# Riser.net
KiCad netlist of a schematic drawn in Altium Designer
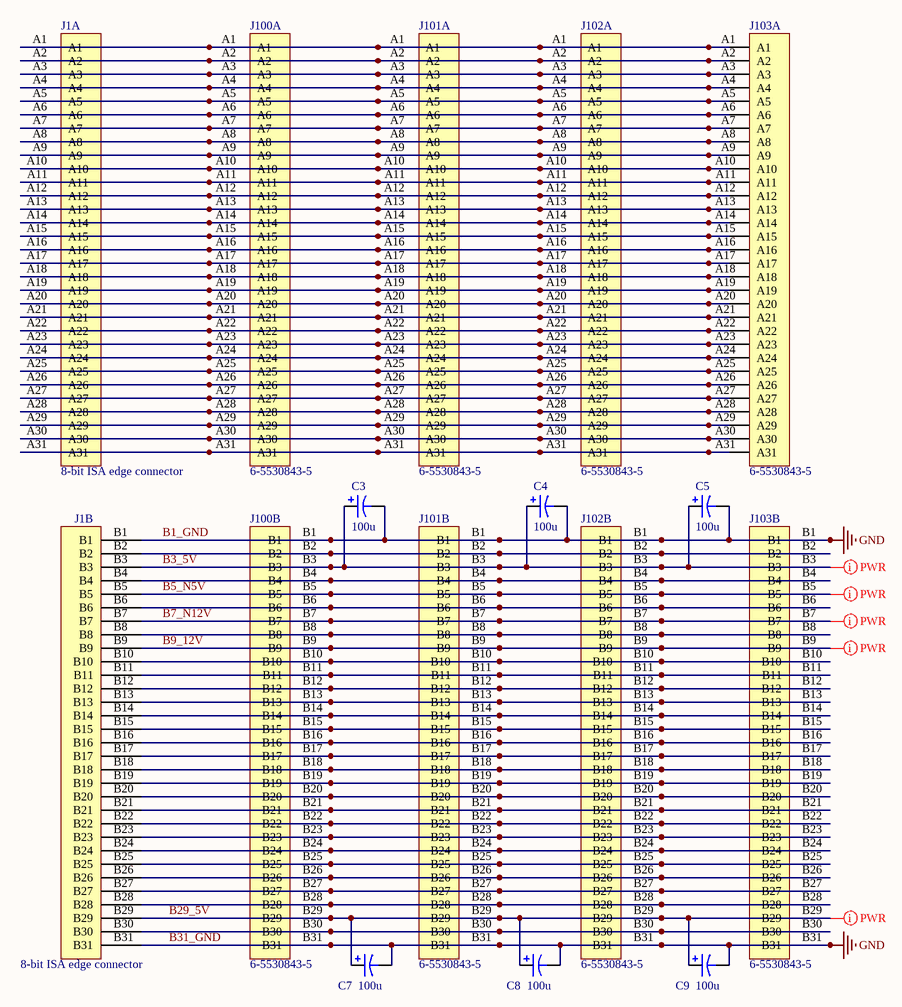
[diagram p0: Riser.SchDoc]

(export (version "E")
  (design (tool "Eeschema 10.0.6"))
  (components
    (comp (ref "C3")
      (value "100u")
      (footprint "CAP-6.3-2.5")
      (description "Polarized Capacitor (Radial)")
      (fields (field (name "PUBLISHER") "Altium Limited"))
      (libsource (lib "Miscellaneous Devices") (part "Cap Pol1"))
    )
    (comp (ref "C4")
      (value "100u")
      (footprint "CAP-6.3-2.5")
      (description "Polarized Capacitor (Radial)")
      (fields (field (name "PUBLISHER") "Altium Limited"))
      (libsource (lib "Miscellaneous Devices") (part "Cap Pol1"))
    )
    (comp (ref "C5")
      (value "100u")
      (footprint "CAP-6.3-2.5")
      (description "Polarized Capacitor (Radial)")
      (fields (field (name "PUBLISHER") "Altium Limited"))
      (libsource (lib "Miscellaneous Devices") (part "Cap Pol1"))
    )
    (comp (ref "C7")
      (value "100u")
      (footprint "CAP-6.3-2.5")
      (description "Polarized Capacitor (Radial)")
      (fields (field (name "PUBLISHER") "Altium Limited"))
      (libsource (lib "Miscellaneous Devices") (part "Cap Pol1"))
    )
    (comp (ref "C8")
      (value "100u")
      (footprint "CAP-6.3-2.5")
      (description "Polarized Capacitor (Radial)")
      (fields (field (name "PUBLISHER") "Altium Limited"))
      (libsource (lib "Miscellaneous Devices") (part "Cap Pol1"))
    )
    (comp (ref "C9")
      (value "100u")
      (footprint "CAP-6.3-2.5")
      (description "Polarized Capacitor (Radial)")
      (fields (field (name "PUBLISHER") "Altium Limited"))
      (libsource (lib "Miscellaneous Devices") (part "Cap Pol1"))
    )
    (comp (ref "J1")
      (value "8-bit ISA edge connector")
      (footprint "ISA-EDGE-62")
      (libsource (lib "6-5530843-5") (part "ISA-EDGE-62"))
    )
    (comp (ref "J100")
      (value "6-5530843-5")
      (footprint "CONN62_6-5530843-5_TEC")
      (description "No Description Available")
      (libsource (lib "6-5530843-5") (part "6-5530843-5"))
    )
    (comp (ref "J101")
      (value "6-5530843-5")
      (footprint "CONN62_6-5530843-5_TEC")
      (description "No Description Available")
      (libsource (lib "6-5530843-5") (part "6-5530843-5"))
    )
    (comp (ref "J102")
      (value "6-5530843-5")
      (footprint "CONN62_6-5530843-5_TEC")
      (description "No Description Available")
      (libsource (lib "6-5530843-5") (part "6-5530843-5"))
    )
    (comp (ref "J103")
      (value "6-5530843-5")
      (footprint "CONN62_6-5530843-5_TEC")
      (description "No Description Available")
      (libsource (lib "6-5530843-5") (part "6-5530843-5"))
    )
  )
  (nets
    (net (code "1") (name "/B3_5V") (class "Default")
      (node (ref "C3") (pin "1") (pinfunction "1_1") (pintype "passive"))
      (node (ref "C4") (pin "1") (pinfunction "1_1") (pintype "passive"))
      (node (ref "C5") (pin "1") (pinfunction "1_1") (pintype "passive"))
      (node (ref "J1") (pin "B3") (pinfunction "B3_B3") (pintype "passive"))
      (node (ref "J100") (pin "B3") (pinfunction "B3_B3") (pintype "passive"))
      (node (ref "J101") (pin "B3") (pinfunction "B3_B3") (pintype "passive"))
      (node (ref "J102") (pin "B3") (pinfunction "B3_B3") (pintype "passive"))
      (node (ref "J103") (pin "B3") (pinfunction "B3_B3") (pintype "passive"))
    )
    (net (code "2") (name "/B5_N5V") (class "Default")
      (node (ref "J1") (pin "B5") (pinfunction "B5_B5") (pintype "passive"))
      (node (ref "J100") (pin "B5") (pinfunction "B5_B5") (pintype "passive"))
      (node (ref "J101") (pin "B5") (pinfunction "B5_B5") (pintype "passive"))
      (node (ref "J102") (pin "B5") (pinfunction "B5_B5") (pintype "passive"))
      (node (ref "J103") (pin "B5") (pinfunction "B5_B5") (pintype "passive"))
    )
    (net (code "3") (name "/B7_N12V") (class "Default")
      (node (ref "J1") (pin "B7") (pinfunction "B7_B7") (pintype "passive"))
      (node (ref "J100") (pin "B7") (pinfunction "B7_B7") (pintype "passive"))
      (node (ref "J101") (pin "B7") (pinfunction "B7_B7") (pintype "passive"))
      (node (ref "J102") (pin "B7") (pinfunction "B7_B7") (pintype "passive"))
      (node (ref "J103") (pin "B7") (pinfunction "B7_B7") (pintype "passive"))
    )
    (net (code "4") (name "/B9_12V") (class "Default")
      (node (ref "J1") (pin "B9") (pinfunction "B9_B9") (pintype "passive"))
      (node (ref "J100") (pin "B9") (pinfunction "B9_B9") (pintype "passive"))
      (node (ref "J101") (pin "B9") (pinfunction "B9_B9") (pintype "passive"))
      (node (ref "J102") (pin "B9") (pinfunction "B9_B9") (pintype "passive"))
      (node (ref "J103") (pin "B9") (pinfunction "B9_B9") (pintype "passive"))
    )
    (net (code "5") (name "/B29_5V") (class "Default")
      (node (ref "C7") (pin "1") (pinfunction "1_1") (pintype "passive"))
      (node (ref "C8") (pin "1") (pinfunction "1_1") (pintype "passive"))
      (node (ref "C9") (pin "1") (pinfunction "1_1") (pintype "passive"))
      (node (ref "J1") (pin "B29") (pinfunction "B29_B29") (pintype "passive"))
      (node (ref "J100") (pin "B29") (pinfunction "B29_B29") (pintype "passive"))
      (node (ref "J101") (pin "B29") (pinfunction "B29_B29") (pintype "passive"))
      (node (ref "J102") (pin "B29") (pinfunction "B29_B29") (pintype "passive"))
      (node (ref "J103") (pin "B29") (pinfunction "B29_B29") (pintype "passive"))
    )
    (net (code "6") (name "GND") (class "Default")
      (node (ref "C3") (pin "2") (pinfunction "2_2") (pintype "passive"))
      (node (ref "C4") (pin "2") (pinfunction "2_2") (pintype "passive"))
      (node (ref "C5") (pin "2") (pinfunction "2_2") (pintype "passive"))
      (node (ref "C7") (pin "2") (pinfunction "2_2") (pintype "passive"))
      (node (ref "C8") (pin "2") (pinfunction "2_2") (pintype "passive"))
      (node (ref "C9") (pin "2") (pinfunction "2_2") (pintype "passive"))
      (node (ref "J1") (pin "B1") (pinfunction "B1_B1") (pintype "passive"))
      (node (ref "J1") (pin "B31") (pinfunction "B31_B31") (pintype "passive"))
      (node (ref "J100") (pin "B1") (pinfunction "B1_B1") (pintype "passive"))
      (node (ref "J100") (pin "B31") (pinfunction "B31_B31") (pintype "passive"))
      (node (ref "J101") (pin "B1") (pinfunction "B1_B1") (pintype "passive"))
      (node (ref "J101") (pin "B31") (pinfunction "B31_B31") (pintype "passive"))
      (node (ref "J102") (pin "B1") (pinfunction "B1_B1") (pintype "passive"))
      (node (ref "J102") (pin "B31") (pinfunction "B31_B31") (pintype "passive"))
      (node (ref "J103") (pin "B1") (pinfunction "B1_B1") (pintype "passive"))
      (node (ref "J103") (pin "B31") (pinfunction "B31_B31") (pintype "passive"))
    )
    (net (code "7") (name "Net-(J1-PadA1)") (class "Default")
      (node (ref "J1") (pin "A1") (pinfunction "A1_A1") (pintype "passive"))
      (node (ref "J100") (pin "A1") (pinfunction "A1_A1") (pintype "passive"))
      (node (ref "J101") (pin "A1") (pinfunction "A1_A1") (pintype "passive"))
      (node (ref "J102") (pin "A1") (pinfunction "A1_A1") (pintype "passive"))
      (node (ref "J103") (pin "A1") (pinfunction "A1_A1") (pintype "passive"))
    )
    (net (code "8") (name "Net-(J1-PadA2)") (class "Default")
      (node (ref "J1") (pin "A2") (pinfunction "A2_A2") (pintype "passive"))
      (node (ref "J100") (pin "A2") (pinfunction "A2_A2") (pintype "passive"))
      (node (ref "J101") (pin "A2") (pinfunction "A2_A2") (pintype "passive"))
      (node (ref "J102") (pin "A2") (pinfunction "A2_A2") (pintype "passive"))
      (node (ref "J103") (pin "A2") (pinfunction "A2_A2") (pintype "passive"))
    )
    (net (code "9") (name "Net-(J1-PadA3)") (class "Default")
      (node (ref "J1") (pin "A3") (pinfunction "A3_A3") (pintype "passive"))
      (node (ref "J100") (pin "A3") (pinfunction "A3_A3") (pintype "passive"))
      (node (ref "J101") (pin "A3") (pinfunction "A3_A3") (pintype "passive"))
      (node (ref "J102") (pin "A3") (pinfunction "A3_A3") (pintype "passive"))
      (node (ref "J103") (pin "A3") (pinfunction "A3_A3") (pintype "passive"))
    )
    (net (code "10") (name "Net-(J1-PadA4)") (class "Default")
      (node (ref "J1") (pin "A4") (pinfunction "A4_A4") (pintype "passive"))
      (node (ref "J100") (pin "A4") (pinfunction "A4_A4") (pintype "passive"))
      (node (ref "J101") (pin "A4") (pinfunction "A4_A4") (pintype "passive"))
      (node (ref "J102") (pin "A4") (pinfunction "A4_A4") (pintype "passive"))
      (node (ref "J103") (pin "A4") (pinfunction "A4_A4") (pintype "passive"))
    )
    (net (code "11") (name "Net-(J1-PadA5)") (class "Default")
      (node (ref "J1") (pin "A5") (pinfunction "A5_A5") (pintype "passive"))
      (node (ref "J100") (pin "A5") (pinfunction "A5_A5") (pintype "passive"))
      (node (ref "J101") (pin "A5") (pinfunction "A5_A5") (pintype "passive"))
      (node (ref "J102") (pin "A5") (pinfunction "A5_A5") (pintype "passive"))
      (node (ref "J103") (pin "A5") (pinfunction "A5_A5") (pintype "passive"))
    )
    (net (code "12") (name "Net-(J1-PadA6)") (class "Default")
      (node (ref "J1") (pin "A6") (pinfunction "A6_A6") (pintype "passive"))
      (node (ref "J100") (pin "A6") (pinfunction "A6_A6") (pintype "passive"))
      (node (ref "J101") (pin "A6") (pinfunction "A6_A6") (pintype "passive"))
      (node (ref "J102") (pin "A6") (pinfunction "A6_A6") (pintype "passive"))
      (node (ref "J103") (pin "A6") (pinfunction "A6_A6") (pintype "passive"))
    )
    (net (code "13") (name "Net-(J1-PadA7)") (class "Default")
      (node (ref "J1") (pin "A7") (pinfunction "A7_A7") (pintype "passive"))
      (node (ref "J100") (pin "A7") (pinfunction "A7_A7") (pintype "passive"))
      (node (ref "J101") (pin "A7") (pinfunction "A7_A7") (pintype "passive"))
      (node (ref "J102") (pin "A7") (pinfunction "A7_A7") (pintype "passive"))
      (node (ref "J103") (pin "A7") (pinfunction "A7_A7") (pintype "passive"))
    )
    (net (code "14") (name "Net-(J1-PadA8)") (class "Default")
      (node (ref "J1") (pin "A8") (pinfunction "A8_A8") (pintype "passive"))
      (node (ref "J100") (pin "A8") (pinfunction "A8_A8") (pintype "passive"))
      (node (ref "J101") (pin "A8") (pinfunction "A8_A8") (pintype "passive"))
      (node (ref "J102") (pin "A8") (pinfunction "A8_A8") (pintype "passive"))
      (node (ref "J103") (pin "A8") (pinfunction "A8_A8") (pintype "passive"))
    )
    (net (code "15") (name "Net-(J1-PadA9)") (class "Default")
      (node (ref "J1") (pin "A9") (pinfunction "A9_A9") (pintype "passive"))
      (node (ref "J100") (pin "A9") (pinfunction "A9_A9") (pintype "passive"))
      (node (ref "J101") (pin "A9") (pinfunction "A9_A9") (pintype "passive"))
      (node (ref "J102") (pin "A9") (pinfunction "A9_A9") (pintype "passive"))
      (node (ref "J103") (pin "A9") (pinfunction "A9_A9") (pintype "passive"))
    )
    (net (code "16") (name "Net-(J1-PadA10)") (class "Default")
      (node (ref "J1") (pin "A10") (pinfunction "A10_A10") (pintype "passive"))
      (node (ref "J100") (pin "A10") (pinfunction "A10_A10") (pintype "passive"))
      (node (ref "J101") (pin "A10") (pinfunction "A10_A10") (pintype "passive"))
      (node (ref "J102") (pin "A10") (pinfunction "A10_A10") (pintype "passive"))
      (node (ref "J103") (pin "A10") (pinfunction "A10_A10") (pintype "passive"))
    )
    (net (code "17") (name "Net-(J1-PadA11)") (class "Default")
      (node (ref "J1") (pin "A11") (pinfunction "A11_A11") (pintype "passive"))
      (node (ref "J100") (pin "A11") (pinfunction "A11_A11") (pintype "passive"))
      (node (ref "J101") (pin "A11") (pinfunction "A11_A11") (pintype "passive"))
      (node (ref "J102") (pin "A11") (pinfunction "A11_A11") (pintype "passive"))
      (node (ref "J103") (pin "A11") (pinfunction "A11_A11") (pintype "passive"))
    )
    (net (code "18") (name "Net-(J1-PadA12)") (class "Default")
      (node (ref "J1") (pin "A12") (pinfunction "A12_A12") (pintype "passive"))
      (node (ref "J100") (pin "A12") (pinfunction "A12_A12") (pintype "passive"))
      (node (ref "J101") (pin "A12") (pinfunction "A12_A12") (pintype "passive"))
      (node (ref "J102") (pin "A12") (pinfunction "A12_A12") (pintype "passive"))
      (node (ref "J103") (pin "A12") (pinfunction "A12_A12") (pintype "passive"))
    )
    (net (code "19") (name "Net-(J1-PadA13)") (class "Default")
      (node (ref "J1") (pin "A13") (pinfunction "A13_A13") (pintype "passive"))
      (node (ref "J100") (pin "A13") (pinfunction "A13_A13") (pintype "passive"))
      (node (ref "J101") (pin "A13") (pinfunction "A13_A13") (pintype "passive"))
      (node (ref "J102") (pin "A13") (pinfunction "A13_A13") (pintype "passive"))
      (node (ref "J103") (pin "A13") (pinfunction "A13_A13") (pintype "passive"))
    )
    (net (code "20") (name "Net-(J1-PadA14)") (class "Default")
      (node (ref "J1") (pin "A14") (pinfunction "A14_A14") (pintype "passive"))
      (node (ref "J100") (pin "A14") (pinfunction "A14_A14") (pintype "passive"))
      (node (ref "J101") (pin "A14") (pinfunction "A14_A14") (pintype "passive"))
      (node (ref "J102") (pin "A14") (pinfunction "A14_A14") (pintype "passive"))
      (node (ref "J103") (pin "A14") (pinfunction "A14_A14") (pintype "passive"))
    )
    (net (code "21") (name "Net-(J1-PadA15)") (class "Default")
      (node (ref "J1") (pin "A15") (pinfunction "A15_A15") (pintype "passive"))
      (node (ref "J100") (pin "A15") (pinfunction "A15_A15") (pintype "passive"))
      (node (ref "J101") (pin "A15") (pinfunction "A15_A15") (pintype "passive"))
      (node (ref "J102") (pin "A15") (pinfunction "A15_A15") (pintype "passive"))
      (node (ref "J103") (pin "A15") (pinfunction "A15_A15") (pintype "passive"))
    )
    (net (code "22") (name "Net-(J1-PadA16)") (class "Default")
      (node (ref "J1") (pin "A16") (pinfunction "A16_A16") (pintype "passive"))
      (node (ref "J100") (pin "A16") (pinfunction "A16_A16") (pintype "passive"))
      (node (ref "J101") (pin "A16") (pinfunction "A16_A16") (pintype "passive"))
      (node (ref "J102") (pin "A16") (pinfunction "A16_A16") (pintype "passive"))
      (node (ref "J103") (pin "A16") (pinfunction "A16_A16") (pintype "passive"))
    )
    (net (code "23") (name "Net-(J1-PadA17)") (class "Default")
      (node (ref "J1") (pin "A17") (pinfunction "A17_A17") (pintype "passive"))
      (node (ref "J100") (pin "A17") (pinfunction "A17_A17") (pintype "passive"))
      (node (ref "J101") (pin "A17") (pinfunction "A17_A17") (pintype "passive"))
      (node (ref "J102") (pin "A17") (pinfunction "A17_A17") (pintype "passive"))
      (node (ref "J103") (pin "A17") (pinfunction "A17_A17") (pintype "passive"))
    )
    (net (code "24") (name "Net-(J1-PadA18)") (class "Default")
      (node (ref "J1") (pin "A18") (pinfunction "A18_A18") (pintype "passive"))
      (node (ref "J100") (pin "A18") (pinfunction "A18_A18") (pintype "passive"))
      (node (ref "J101") (pin "A18") (pinfunction "A18_A18") (pintype "passive"))
      (node (ref "J102") (pin "A18") (pinfunction "A18_A18") (pintype "passive"))
      (node (ref "J103") (pin "A18") (pinfunction "A18_A18") (pintype "passive"))
    )
    (net (code "25") (name "Net-(J1-PadA19)") (class "Default")
      (node (ref "J1") (pin "A19") (pinfunction "A19_A19") (pintype "passive"))
      (node (ref "J100") (pin "A19") (pinfunction "A19_A19") (pintype "passive"))
      (node (ref "J101") (pin "A19") (pinfunction "A19_A19") (pintype "passive"))
      (node (ref "J102") (pin "A19") (pinfunction "A19_A19") (pintype "passive"))
      (node (ref "J103") (pin "A19") (pinfunction "A19_A19") (pintype "passive"))
    )
    (net (code "26") (name "Net-(J1-PadA20)") (class "Default")
      (node (ref "J1") (pin "A20") (pinfunction "A20_A20") (pintype "passive"))
      (node (ref "J100") (pin "A20") (pinfunction "A20_A20") (pintype "passive"))
      (node (ref "J101") (pin "A20") (pinfunction "A20_A20") (pintype "passive"))
      (node (ref "J102") (pin "A20") (pinfunction "A20_A20") (pintype "passive"))
      (node (ref "J103") (pin "A20") (pinfunction "A20_A20") (pintype "passive"))
    )
    (net (code "27") (name "Net-(J1-PadA21)") (class "Default")
      (node (ref "J1") (pin "A21") (pinfunction "A21_A21") (pintype "passive"))
      (node (ref "J100") (pin "A21") (pinfunction "A21_A21") (pintype "passive"))
      (node (ref "J101") (pin "A21") (pinfunction "A21_A21") (pintype "passive"))
      (node (ref "J102") (pin "A21") (pinfunction "A21_A21") (pintype "passive"))
      (node (ref "J103") (pin "A21") (pinfunction "A21_A21") (pintype "passive"))
    )
    (net (code "28") (name "Net-(J1-PadA22)") (class "Default")
      (node (ref "J1") (pin "A22") (pinfunction "A22_A22") (pintype "passive"))
      (node (ref "J100") (pin "A22") (pinfunction "A22_A22") (pintype "passive"))
      (node (ref "J101") (pin "A22") (pinfunction "A22_A22") (pintype "passive"))
      (node (ref "J102") (pin "A22") (pinfunction "A22_A22") (pintype "passive"))
      (node (ref "J103") (pin "A22") (pinfunction "A22_A22") (pintype "passive"))
    )
    (net (code "29") (name "Net-(J1-PadA23)") (class "Default")
      (node (ref "J1") (pin "A23") (pinfunction "A23_A23") (pintype "passive"))
      (node (ref "J100") (pin "A23") (pinfunction "A23_A23") (pintype "passive"))
      (node (ref "J101") (pin "A23") (pinfunction "A23_A23") (pintype "passive"))
      (node (ref "J102") (pin "A23") (pinfunction "A23_A23") (pintype "passive"))
      (node (ref "J103") (pin "A23") (pinfunction "A23_A23") (pintype "passive"))
    )
    (net (code "30") (name "Net-(J1-PadA24)") (class "Default")
      (node (ref "J1") (pin "A24") (pinfunction "A24_A24") (pintype "passive"))
      (node (ref "J100") (pin "A24") (pinfunction "A24_A24") (pintype "passive"))
      (node (ref "J101") (pin "A24") (pinfunction "A24_A24") (pintype "passive"))
      (node (ref "J102") (pin "A24") (pinfunction "A24_A24") (pintype "passive"))
      (node (ref "J103") (pin "A24") (pinfunction "A24_A24") (pintype "passive"))
    )
    (net (code "31") (name "Net-(J1-PadA25)") (class "Default")
      (node (ref "J1") (pin "A25") (pinfunction "A25_A25") (pintype "passive"))
      (node (ref "J100") (pin "A25") (pinfunction "A25_A25") (pintype "passive"))
      (node (ref "J101") (pin "A25") (pinfunction "A25_A25") (pintype "passive"))
      (node (ref "J102") (pin "A25") (pinfunction "A25_A25") (pintype "passive"))
      (node (ref "J103") (pin "A25") (pinfunction "A25_A25") (pintype "passive"))
    )
    (net (code "32") (name "Net-(J1-PadA26)") (class "Default")
      (node (ref "J1") (pin "A26") (pinfunction "A26_A26") (pintype "passive"))
      (node (ref "J100") (pin "A26") (pinfunction "A26_A26") (pintype "passive"))
      (node (ref "J101") (pin "A26") (pinfunction "A26_A26") (pintype "passive"))
      (node (ref "J102") (pin "A26") (pinfunction "A26_A26") (pintype "passive"))
      (node (ref "J103") (pin "A26") (pinfunction "A26_A26") (pintype "passive"))
    )
    (net (code "33") (name "Net-(J1-PadA27)") (class "Default")
      (node (ref "J1") (pin "A27") (pinfunction "A27_A27") (pintype "passive"))
      (node (ref "J100") (pin "A27") (pinfunction "A27_A27") (pintype "passive"))
      (node (ref "J101") (pin "A27") (pinfunction "A27_A27") (pintype "passive"))
      (node (ref "J102") (pin "A27") (pinfunction "A27_A27") (pintype "passive"))
      (node (ref "J103") (pin "A27") (pinfunction "A27_A27") (pintype "passive"))
    )
    (net (code "34") (name "Net-(J1-PadA28)") (class "Default")
      (node (ref "J1") (pin "A28") (pinfunction "A28_A28") (pintype "passive"))
      (node (ref "J100") (pin "A28") (pinfunction "A28_A28") (pintype "passive"))
      (node (ref "J101") (pin "A28") (pinfunction "A28_A28") (pintype "passive"))
      (node (ref "J102") (pin "A28") (pinfunction "A28_A28") (pintype "passive"))
      (node (ref "J103") (pin "A28") (pinfunction "A28_A28") (pintype "passive"))
    )
    (net (code "35") (name "Net-(J1-PadA29)") (class "Default")
      (node (ref "J1") (pin "A29") (pinfunction "A29_A29") (pintype "passive"))
      (node (ref "J100") (pin "A29") (pinfunction "A29_A29") (pintype "passive"))
      (node (ref "J101") (pin "A29") (pinfunction "A29_A29") (pintype "passive"))
      (node (ref "J102") (pin "A29") (pinfunction "A29_A29") (pintype "passive"))
      (node (ref "J103") (pin "A29") (pinfunction "A29_A29") (pintype "passive"))
    )
    (net (code "36") (name "Net-(J1-PadA30)") (class "Default")
      (node (ref "J1") (pin "A30") (pinfunction "A30_A30") (pintype "passive"))
      (node (ref "J100") (pin "A30") (pinfunction "A30_A30") (pintype "passive"))
      (node (ref "J101") (pin "A30") (pinfunction "A30_A30") (pintype "passive"))
      (node (ref "J102") (pin "A30") (pinfunction "A30_A30") (pintype "passive"))
      (node (ref "J103") (pin "A30") (pinfunction "A30_A30") (pintype "passive"))
    )
    (net (code "37") (name "Net-(J1-PadA31)") (class "Default")
      (node (ref "J1") (pin "A31") (pinfunction "A31_A31") (pintype "passive"))
      (node (ref "J100") (pin "A31") (pinfunction "A31_A31") (pintype "passive"))
      (node (ref "J101") (pin "A31") (pinfunction "A31_A31") (pintype "passive"))
      (node (ref "J102") (pin "A31") (pinfunction "A31_A31") (pintype "passive"))
      (node (ref "J103") (pin "A31") (pinfunction "A31_A31") (pintype "passive"))
    )
    (net (code "38") (name "Net-(J1-PadB2)") (class "Default")
      (node (ref "J1") (pin "B2") (pinfunction "B2_B2") (pintype "passive"))
      (node (ref "J100") (pin "B2") (pinfunction "B2_B2") (pintype "passive"))
      (node (ref "J101") (pin "B2") (pinfunction "B2_B2") (pintype "passive"))
      (node (ref "J102") (pin "B2") (pinfunction "B2_B2") (pintype "passive"))
      (node (ref "J103") (pin "B2") (pinfunction "B2_B2") (pintype "passive"))
    )
    (net (code "39") (name "Net-(J1-PadB4)") (class "Default")
      (node (ref "J1") (pin "B4") (pinfunction "B4_B4") (pintype "passive"))
      (node (ref "J100") (pin "B4") (pinfunction "B4_B4") (pintype "passive"))
      (node (ref "J101") (pin "B4") (pinfunction "B4_B4") (pintype "passive"))
      (node (ref "J102") (pin "B4") (pinfunction "B4_B4") (pintype "passive"))
      (node (ref "J103") (pin "B4") (pinfunction "B4_B4") (pintype "passive"))
    )
    (net (code "40") (name "Net-(J1-PadB6)") (class "Default")
      (node (ref "J1") (pin "B6") (pinfunction "B6_B6") (pintype "passive"))
      (node (ref "J100") (pin "B6") (pinfunction "B6_B6") (pintype "passive"))
      (node (ref "J101") (pin "B6") (pinfunction "B6_B6") (pintype "passive"))
      (node (ref "J102") (pin "B6") (pinfunction "B6_B6") (pintype "passive"))
      (node (ref "J103") (pin "B6") (pinfunction "B6_B6") (pintype "passive"))
    )
    (net (code "41") (name "Net-(J1-PadB8)") (class "Default")
      (node (ref "J1") (pin "B8") (pinfunction "B8_B8") (pintype "passive"))
      (node (ref "J100") (pin "B8") (pinfunction "B8_B8") (pintype "passive"))
      (node (ref "J101") (pin "B8") (pinfunction "B8_B8") (pintype "passive"))
      (node (ref "J102") (pin "B8") (pinfunction "B8_B8") (pintype "passive"))
      (node (ref "J103") (pin "B8") (pinfunction "B8_B8") (pintype "passive"))
    )
    (net (code "42") (name "Net-(J1-PadB10)") (class "Default")
      (node (ref "J1") (pin "B10") (pinfunction "B10_B10") (pintype "passive"))
      (node (ref "J100") (pin "B10") (pinfunction "B10_B10") (pintype "passive"))
      (node (ref "J101") (pin "B10") (pinfunction "B10_B10") (pintype "passive"))
      (node (ref "J102") (pin "B10") (pinfunction "B10_B10") (pintype "passive"))
      (node (ref "J103") (pin "B10") (pinfunction "B10_B10") (pintype "passive"))
    )
    (net (code "43") (name "Net-(J1-PadB11)") (class "Default")
      (node (ref "J1") (pin "B11") (pinfunction "B11_B11") (pintype "passive"))
      (node (ref "J100") (pin "B11") (pinfunction "B11_B11") (pintype "passive"))
      (node (ref "J101") (pin "B11") (pinfunction "B11_B11") (pintype "passive"))
      (node (ref "J102") (pin "B11") (pinfunction "B11_B11") (pintype "passive"))
      (node (ref "J103") (pin "B11") (pinfunction "B11_B11") (pintype "passive"))
    )
    (net (code "44") (name "Net-(J1-PadB12)") (class "Default")
      (node (ref "J1") (pin "B12") (pinfunction "B12_B12") (pintype "passive"))
      (node (ref "J100") (pin "B12") (pinfunction "B12_B12") (pintype "passive"))
      (node (ref "J101") (pin "B12") (pinfunction "B12_B12") (pintype "passive"))
      (node (ref "J102") (pin "B12") (pinfunction "B12_B12") (pintype "passive"))
      (node (ref "J103") (pin "B12") (pinfunction "B12_B12") (pintype "passive"))
    )
    (net (code "45") (name "Net-(J1-PadB13)") (class "Default")
      (node (ref "J1") (pin "B13") (pinfunction "B13_B13") (pintype "passive"))
      (node (ref "J100") (pin "B13") (pinfunction "B13_B13") (pintype "passive"))
      (node (ref "J101") (pin "B13") (pinfunction "B13_B13") (pintype "passive"))
      (node (ref "J102") (pin "B13") (pinfunction "B13_B13") (pintype "passive"))
      (node (ref "J103") (pin "B13") (pinfunction "B13_B13") (pintype "passive"))
    )
    (net (code "46") (name "Net-(J1-PadB14)") (class "Default")
      (node (ref "J1") (pin "B14") (pinfunction "B14_B14") (pintype "passive"))
      (node (ref "J100") (pin "B14") (pinfunction "B14_B14") (pintype "passive"))
      (node (ref "J101") (pin "B14") (pinfunction "B14_B14") (pintype "passive"))
      (node (ref "J102") (pin "B14") (pinfunction "B14_B14") (pintype "passive"))
      (node (ref "J103") (pin "B14") (pinfunction "B14_B14") (pintype "passive"))
    )
    (net (code "47") (name "Net-(J1-PadB15)") (class "Default")
      (node (ref "J1") (pin "B15") (pinfunction "B15_B15") (pintype "passive"))
      (node (ref "J100") (pin "B15") (pinfunction "B15_B15") (pintype "passive"))
      (node (ref "J101") (pin "B15") (pinfunction "B15_B15") (pintype "passive"))
      (node (ref "J102") (pin "B15") (pinfunction "B15_B15") (pintype "passive"))
      (node (ref "J103") (pin "B15") (pinfunction "B15_B15") (pintype "passive"))
    )
    (net (code "48") (name "Net-(J1-PadB16)") (class "Default")
      (node (ref "J1") (pin "B16") (pinfunction "B16_B16") (pintype "passive"))
      (node (ref "J100") (pin "B16") (pinfunction "B16_B16") (pintype "passive"))
      (node (ref "J101") (pin "B16") (pinfunction "B16_B16") (pintype "passive"))
      (node (ref "J102") (pin "B16") (pinfunction "B16_B16") (pintype "passive"))
      (node (ref "J103") (pin "B16") (pinfunction "B16_B16") (pintype "passive"))
    )
    (net (code "49") (name "Net-(J1-PadB17)") (class "Default")
      (node (ref "J1") (pin "B17") (pinfunction "B17_B17") (pintype "passive"))
      (node (ref "J100") (pin "B17") (pinfunction "B17_B17") (pintype "passive"))
      (node (ref "J101") (pin "B17") (pinfunction "B17_B17") (pintype "passive"))
      (node (ref "J102") (pin "B17") (pinfunction "B17_B17") (pintype "passive"))
      (node (ref "J103") (pin "B17") (pinfunction "B17_B17") (pintype "passive"))
    )
    (net (code "50") (name "Net-(J1-PadB18)") (class "Default")
      (node (ref "J1") (pin "B18") (pinfunction "B18_B18") (pintype "passive"))
      (node (ref "J100") (pin "B18") (pinfunction "B18_B18") (pintype "passive"))
      (node (ref "J101") (pin "B18") (pinfunction "B18_B18") (pintype "passive"))
      (node (ref "J102") (pin "B18") (pinfunction "B18_B18") (pintype "passive"))
      (node (ref "J103") (pin "B18") (pinfunction "B18_B18") (pintype "passive"))
    )
    (net (code "51") (name "Net-(J1-PadB19)") (class "Default")
      (node (ref "J1") (pin "B19") (pinfunction "B19_B19") (pintype "passive"))
      (node (ref "J100") (pin "B19") (pinfunction "B19_B19") (pintype "passive"))
      (node (ref "J101") (pin "B19") (pinfunction "B19_B19") (pintype "passive"))
      (node (ref "J102") (pin "B19") (pinfunction "B19_B19") (pintype "passive"))
      (node (ref "J103") (pin "B19") (pinfunction "B19_B19") (pintype "passive"))
    )
    (net (code "52") (name "Net-(J1-PadB20)") (class "Default")
      (node (ref "J1") (pin "B20") (pinfunction "B20_B20") (pintype "passive"))
      (node (ref "J100") (pin "B20") (pinfunction "B20_B20") (pintype "passive"))
      (node (ref "J101") (pin "B20") (pinfunction "B20_B20") (pintype "passive"))
      (node (ref "J102") (pin "B20") (pinfunction "B20_B20") (pintype "passive"))
      (node (ref "J103") (pin "B20") (pinfunction "B20_B20") (pintype "passive"))
    )
    (net (code "53") (name "Net-(J1-PadB21)") (class "Default")
      (node (ref "J1") (pin "B21") (pinfunction "B21_B21") (pintype "passive"))
      (node (ref "J100") (pin "B21") (pinfunction "B21_B21") (pintype "passive"))
      (node (ref "J101") (pin "B21") (pinfunction "B21_B21") (pintype "passive"))
      (node (ref "J102") (pin "B21") (pinfunction "B21_B21") (pintype "passive"))
      (node (ref "J103") (pin "B21") (pinfunction "B21_B21") (pintype "passive"))
    )
    (net (code "54") (name "Net-(J1-PadB22)") (class "Default")
      (node (ref "J1") (pin "B22") (pinfunction "B22_B22") (pintype "passive"))
      (node (ref "J100") (pin "B22") (pinfunction "B22_B22") (pintype "passive"))
      (node (ref "J101") (pin "B22") (pinfunction "B22_B22") (pintype "passive"))
      (node (ref "J102") (pin "B22") (pinfunction "B22_B22") (pintype "passive"))
      (node (ref "J103") (pin "B22") (pinfunction "B22_B22") (pintype "passive"))
    )
    (net (code "55") (name "Net-(J1-PadB23)") (class "Default")
      (node (ref "J1") (pin "B23") (pinfunction "B23_B23") (pintype "passive"))
      (node (ref "J100") (pin "B23") (pinfunction "B23_B23") (pintype "passive"))
      (node (ref "J101") (pin "B23") (pinfunction "B23_B23") (pintype "passive"))
      (node (ref "J102") (pin "B23") (pinfunction "B23_B23") (pintype "passive"))
      (node (ref "J103") (pin "B23") (pinfunction "B23_B23") (pintype "passive"))
    )
    (net (code "56") (name "Net-(J1-PadB24)") (class "Default")
      (node (ref "J1") (pin "B24") (pinfunction "B24_B24") (pintype "passive"))
      (node (ref "J100") (pin "B24") (pinfunction "B24_B24") (pintype "passive"))
      (node (ref "J101") (pin "B24") (pinfunction "B24_B24") (pintype "passive"))
      (node (ref "J102") (pin "B24") (pinfunction "B24_B24") (pintype "passive"))
      (node (ref "J103") (pin "B24") (pinfunction "B24_B24") (pintype "passive"))
    )
    (net (code "57") (name "Net-(J1-PadB25)") (class "Default")
      (node (ref "J1") (pin "B25") (pinfunction "B25_B25") (pintype "passive"))
      (node (ref "J100") (pin "B25") (pinfunction "B25_B25") (pintype "passive"))
      (node (ref "J101") (pin "B25") (pinfunction "B25_B25") (pintype "passive"))
      (node (ref "J102") (pin "B25") (pinfunction "B25_B25") (pintype "passive"))
      (node (ref "J103") (pin "B25") (pinfunction "B25_B25") (pintype "passive"))
    )
    (net (code "58") (name "Net-(J1-PadB26)") (class "Default")
      (node (ref "J1") (pin "B26") (pinfunction "B26_B26") (pintype "passive"))
      (node (ref "J100") (pin "B26") (pinfunction "B26_B26") (pintype "passive"))
      (node (ref "J101") (pin "B26") (pinfunction "B26_B26") (pintype "passive"))
      (node (ref "J102") (pin "B26") (pinfunction "B26_B26") (pintype "passive"))
      (node (ref "J103") (pin "B26") (pinfunction "B26_B26") (pintype "passive"))
    )
    (net (code "59") (name "Net-(J1-PadB27)") (class "Default")
      (node (ref "J1") (pin "B27") (pinfunction "B27_B27") (pintype "passive"))
      (node (ref "J100") (pin "B27") (pinfunction "B27_B27") (pintype "passive"))
      (node (ref "J101") (pin "B27") (pinfunction "B27_B27") (pintype "passive"))
      (node (ref "J102") (pin "B27") (pinfunction "B27_B27") (pintype "passive"))
      (node (ref "J103") (pin "B27") (pinfunction "B27_B27") (pintype "passive"))
    )
    (net (code "60") (name "Net-(J1-PadB28)") (class "Default")
      (node (ref "J1") (pin "B28") (pinfunction "B28_B28") (pintype "passive"))
      (node (ref "J100") (pin "B28") (pinfunction "B28_B28") (pintype "passive"))
      (node (ref "J101") (pin "B28") (pinfunction "B28_B28") (pintype "passive"))
      (node (ref "J102") (pin "B28") (pinfunction "B28_B28") (pintype "passive"))
      (node (ref "J103") (pin "B28") (pinfunction "B28_B28") (pintype "passive"))
    )
    (net (code "61") (name "Net-(J1-PadB30)") (class "Default")
      (node (ref "J1") (pin "B30") (pinfunction "B30_B30") (pintype "passive"))
      (node (ref "J100") (pin "B30") (pinfunction "B30_B30") (pintype "passive"))
      (node (ref "J101") (pin "B30") (pinfunction "B30_B30") (pintype "passive"))
      (node (ref "J102") (pin "B30") (pinfunction "B30_B30") (pintype "passive"))
      (node (ref "J103") (pin "B30") (pinfunction "B30_B30") (pintype "passive"))
    )
  )
)
